# ADC.net
KiCad netlist of a schematic drawn in Altium Designer
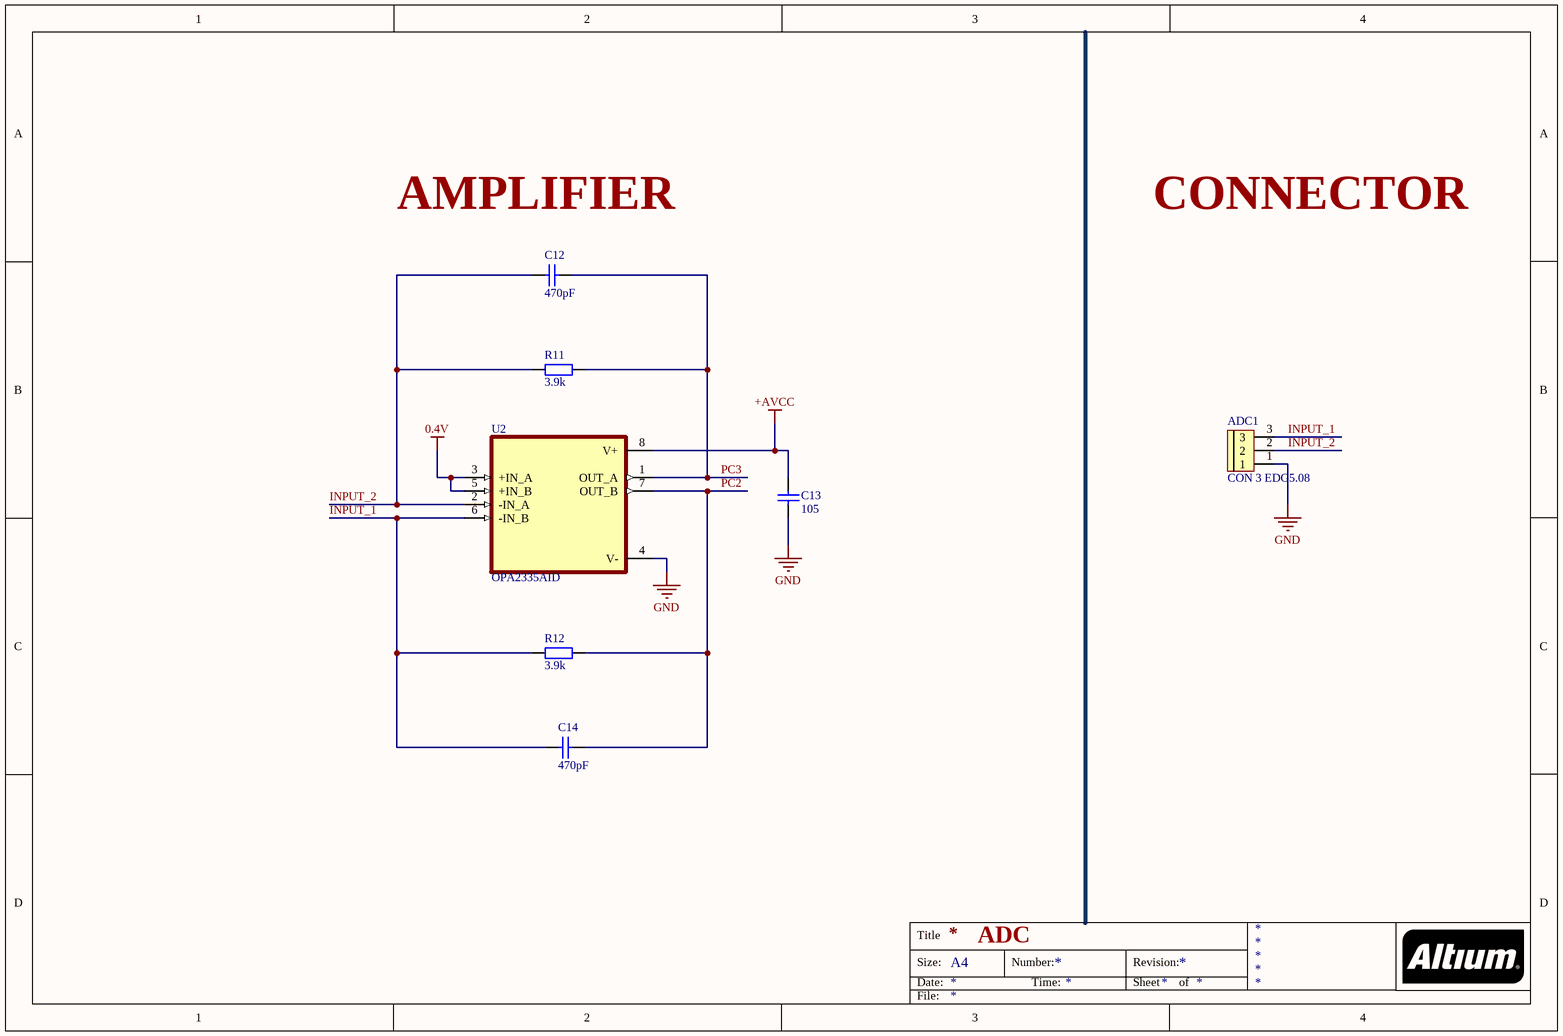
[diagram p0: ADC.SchDoc]

(export (version "E")
  (design (tool "Eeschema 10.0.6"))
  (components
    (comp (ref "ADC1")
      (value "CON 3 EDG5.08")
      (footprint "CON 3 3EDG5.08")
      (description "Cắm")
      (libsource (lib "Altium_Lib_by_KhueNguyenCreator") (part "CON 3 EDG5.08"))
    )
    (comp (ref "C12")
      (value "470pF")
      (footprint "tu 0603")
      (description "Dán")
      (libsource (lib "Altium_Lib_by_KhueNguyenCreator") (part "Tu 0603 470pF 50V 10%"))
    )
    (comp (ref "C13")
      (value "105")
      (footprint "tu 1206")
      (description "Dán")
      (libsource (lib "Altium_Lib_by_KhueNguyenCreator") (part "Tu 1206 105 50V 20%"))
    )
    (comp (ref "C14")
      (value "470pF")
      (footprint "tu 0603")
      (description "Dán")
      (libsource (lib "Altium_Lib_by_KhueNguyenCreator") (part "Tu 0603 470pF 50V 10%"))
    )
    (comp (ref "R11")
      (value "3.9k")
      (footprint "tro smd 0603")
      (description "Dán")
      (libsource (lib "Altium_Lib_by_KhueNguyenCreator") (part "Tro 0603 1% 3.9k"))
    )
    (comp (ref "R12")
      (value "3.9k")
      (footprint "tro smd 0603")
      (description "Dán")
      (libsource (lib "Altium_Lib_by_KhueNguyenCreator") (part "Tro 0603 1% 3.9k"))
    )
    (comp (ref "U2")
      (value "OPA2335AID")
      (footprint "SOIC127P599X175-8N")
      (fields (field (name "MF") "{'manufacturer': u'Texas Instruments'}"))
      (libsource (lib "SnapEDA_Library") (part "OPA2335AID"))
    )
  )
  (nets
    (net (code "1") (name "+AVCC") (class "Default")
      (node (ref "C13") (pin "1") (pinfunction "1_1") (pintype "passive"))
      (node (ref "U2") (pin "8") (pinfunction "V+_8") (pintype "power_in"))
    )
    (net (code "2") (name "/INPUT_1") (class "Default")
      (node (ref "ADC1") (pin "3") (pinfunction "3_3") (pintype "passive"))
      (node (ref "C14") (pin "2") (pinfunction "2_2") (pintype "passive"))
      (node (ref "R12") (pin "1") (pinfunction "1_1") (pintype "passive"))
      (node (ref "U2") (pin "6") (pinfunction "-IN_B_6") (pintype "input"))
    )
    (net (code "3") (name "/INPUT_2") (class "Default")
      (node (ref "ADC1") (pin "2") (pinfunction "2_2") (pintype "passive"))
      (node (ref "C12") (pin "2") (pinfunction "2_2") (pintype "passive"))
      (node (ref "R11") (pin "1") (pinfunction "1_1") (pintype "passive"))
      (node (ref "U2") (pin "2") (pinfunction "-IN_A_2") (pintype "input"))
    )
    (net (code "4") (name "/PC2") (class "Default")
      (node (ref "C14") (pin "1") (pinfunction "1_1") (pintype "passive"))
      (node (ref "R12") (pin "2") (pinfunction "2_2") (pintype "passive"))
      (node (ref "U2") (pin "7") (pinfunction "OUT_B_7") (pintype "output"))
    )
    (net (code "5") (name "/PC3") (class "Default")
      (node (ref "C12") (pin "1") (pinfunction "1_1") (pintype "passive"))
      (node (ref "R11") (pin "2") (pinfunction "2_2") (pintype "passive"))
      (node (ref "U2") (pin "1") (pinfunction "OUT_A_1") (pintype "output"))
    )
    (net (code "6") (name "0.4V") (class "Default")
      (node (ref "U2") (pin "3") (pinfunction "+IN_A_3") (pintype "input"))
      (node (ref "U2") (pin "5") (pinfunction "+IN_B_5") (pintype "input"))
    )
    (net (code "7") (name "GND") (class "Default")
      (node (ref "ADC1") (pin "1") (pinfunction "1_1") (pintype "passive"))
      (node (ref "C13") (pin "2") (pinfunction "2_2") (pintype "passive"))
      (node (ref "U2") (pin "4") (pinfunction "V-_4") (pintype "power_in"))
    )
  )
)
